# Superbot_LEDS.net
KiCad netlist of a schematic drawn in Altium Designer
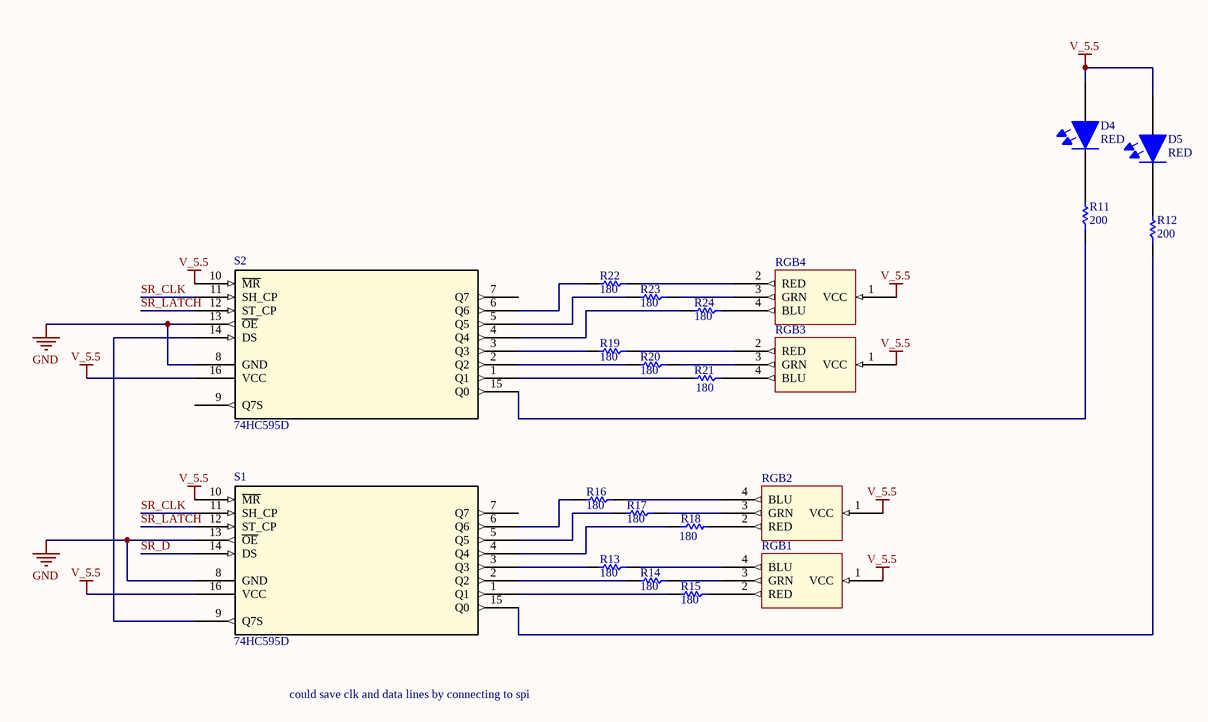
[diagram p0: Superbot_LEDS.SchDoc]

(export (version "E")
  (design (tool "Eeschema 10.0.6"))
  (components
    (comp (ref "D4")
      (value "RED")
      (footprint "LED0603")
      (description "LED")
      (libsource (lib "SuperBot_Schlib1") (part "LED"))
    )
    (comp (ref "D5")
      (value "RED")
      (footprint "LED0603")
      (description "LED")
      (libsource (lib "SuperBot_Schlib1") (part "LED"))
    )
    (comp (ref "R11")
      (value "200")
      (footprint "RES0603R")
      (description "Resistor")
      (libsource (lib "SuperBot_Schlib1") (part "R"))
    )
    (comp (ref "R12")
      (value "200")
      (footprint "RES0603R")
      (description "Resistor")
      (libsource (lib "SuperBot_Schlib1") (part "R"))
    )
    (comp (ref "R13")
      (value "180")
      (footprint "RES0603R")
      (description "Resistor")
      (libsource (lib "SuperBot_Schlib1") (part "R"))
    )
    (comp (ref "R14")
      (value "180")
      (footprint "RES0603R")
      (description "Resistor")
      (libsource (lib "SuperBot_Schlib1") (part "R"))
    )
    (comp (ref "R15")
      (value "180")
      (footprint "RES0603R")
      (description "Resistor")
      (libsource (lib "SuperBot_Schlib1") (part "R"))
    )
    (comp (ref "R16")
      (value "180")
      (footprint "RES0603R")
      (description "Resistor")
      (libsource (lib "SuperBot_Schlib1") (part "R"))
    )
    (comp (ref "R17")
      (value "180")
      (footprint "RES0603R")
      (description "Resistor")
      (libsource (lib "SuperBot_Schlib1") (part "R"))
    )
    (comp (ref "R18")
      (value "180")
      (footprint "RES0603R")
      (description "Resistor")
      (libsource (lib "SuperBot_Schlib1") (part "R"))
    )
    (comp (ref "R19")
      (value "180")
      (footprint "RES0603R")
      (description "Resistor")
      (libsource (lib "SuperBot_Schlib1") (part "R"))
    )
    (comp (ref "R20")
      (value "180")
      (footprint "RES0603R")
      (description "Resistor")
      (libsource (lib "SuperBot_Schlib1") (part "R"))
    )
    (comp (ref "R21")
      (value "180")
      (footprint "RES0603R")
      (description "Resistor")
      (libsource (lib "SuperBot_Schlib1") (part "R"))
    )
    (comp (ref "R22")
      (value "180")
      (footprint "RES0603R")
      (description "Resistor")
      (libsource (lib "SuperBot_Schlib1") (part "R"))
    )
    (comp (ref "R23")
      (value "180")
      (footprint "RES0603R")
      (description "Resistor")
      (libsource (lib "SuperBot_Schlib1") (part "R"))
    )
    (comp (ref "R24")
      (value "180")
      (footprint "RES0603R")
      (description "Resistor")
      (libsource (lib "SuperBot_Schlib1") (part "R"))
    )
    (comp (ref "RGB1")
      (value "~")
      (footprint "RGB LED")
      (fields
        (field (name "MANUFACTURER") "Cree Inc")
        (field (name "MANUFACTURER PART NUM") "CLV1L-FKB-CJMNQEGBB7673673")
      )
      (libsource (lib "SuperBot_Schlib1") (part "RGB LED"))
    )
    (comp (ref "RGB2")
      (value "~")
      (footprint "RGB LED")
      (fields
        (field (name "MANUFACTURER") "Cree Inc")
        (field (name "MANUFACTURER PART NUM") "CLV1L-FKB-CJMNQEGBB7673673")
      )
      (libsource (lib "SuperBot_Schlib1") (part "RGB LED"))
    )
    (comp (ref "RGB3")
      (value "~")
      (footprint "RGB LED")
      (fields
        (field (name "MANUFACTURER") "Cree Inc")
        (field (name "MANUFACTURER PART NUM") "CLV1L-FKB-CJMNQEGBB7673673")
      )
      (libsource (lib "") (part "RGB LED_1"))
    )
    (comp (ref "RGB4")
      (value "~")
      (footprint "RGB LED")
      (fields
        (field (name "MANUFACTURER") "Cree Inc")
        (field (name "MANUFACTURER PART NUM") "CLV1L-FKB-CJMNQEGBB7673673")
      )
      (libsource (lib "") (part "RGB LED_1"))
    )
    (comp (ref "S1")
      (value "74HC595D")
      (footprint "SOT109-1-M")
      (description "Shift Register")
      (libsource (lib "SuperBot_Schlib1") (part "74HC595D"))
    )
    (comp (ref "S2")
      (value "74HC595D")
      (footprint "SOT109-1-M")
      (description "Shift Register")
      (libsource (lib "SuperBot_Schlib1") (part "74HC595D"))
    )
  )
  (nets
    (net (code "1") (name "/SR_CLK") (class "Default")
      (node (ref "S1") (pin "11") (pinfunction "SH_CP_11") (pintype "input"))
      (node (ref "S2") (pin "11") (pinfunction "SH_CP_11") (pintype "input"))
    )
    (net (code "2") (name "/SR_D") (class "Default")
      (node (ref "S1") (pin "14") (pinfunction "DS_14") (pintype "input"))
    )
    (net (code "3") (name "/SR_LATCH") (class "Default")
      (node (ref "S1") (pin "12") (pinfunction "ST_CP_12") (pintype "input"))
      (node (ref "S2") (pin "12") (pinfunction "ST_CP_12") (pintype "input"))
    )
    (net (code "4") (name "GND") (class "Default")
      (node (ref "S1") (pin "13") (pinfunction "~{OE}_13") (pintype "output"))
      (node (ref "S1") (pin "8") (pinfunction "GND_8") (pintype "power_in"))
      (node (ref "S2") (pin "13") (pinfunction "~{OE}_13") (pintype "output"))
      (node (ref "S2") (pin "8") (pinfunction "GND_8") (pintype "power_in"))
    )
    (net (code "5") (name "Net-(D4-CATHODE)") (class "Default")
      (node (ref "D4") (pin "K") (pinfunction "CATHODE_K") (pintype "passive"))
      (node (ref "R11") (pin "2") (pintype "passive"))
    )
    (net (code "6") (name "Net-(D5-CATHODE)") (class "Default")
      (node (ref "D5") (pin "K") (pinfunction "CATHODE_K") (pintype "passive"))
      (node (ref "R12") (pin "2") (pintype "passive"))
    )
    (net (code "7") (name "Net-(RGB1-BLU)") (class "Default")
      (node (ref "R13") (pin "1") (pintype "passive"))
      (node (ref "RGB1") (pin "4") (pinfunction "BLU_4") (pintype "output"))
    )
    (net (code "8") (name "Net-(RGB1-GRN)") (class "Default")
      (node (ref "R14") (pin "1") (pintype "passive"))
      (node (ref "RGB1") (pin "3") (pinfunction "GRN_3") (pintype "output"))
    )
    (net (code "9") (name "Net-(RGB1-RED)") (class "Default")
      (node (ref "R15") (pin "1") (pintype "passive"))
      (node (ref "RGB1") (pin "2") (pinfunction "RED_2") (pintype "output"))
    )
    (net (code "10") (name "Net-(RGB2-BLU)") (class "Default")
      (node (ref "R16") (pin "1") (pintype "passive"))
      (node (ref "RGB2") (pin "4") (pinfunction "BLU_4") (pintype "output"))
    )
    (net (code "11") (name "Net-(RGB2-GRN)") (class "Default")
      (node (ref "R17") (pin "1") (pintype "passive"))
      (node (ref "RGB2") (pin "3") (pinfunction "GRN_3") (pintype "output"))
    )
    (net (code "12") (name "Net-(RGB2-RED)") (class "Default")
      (node (ref "R18") (pin "2") (pintype "passive"))
      (node (ref "RGB2") (pin "2") (pinfunction "RED_2") (pintype "output"))
    )
    (net (code "13") (name "Net-(RGB3-BLU)") (class "Default")
      (node (ref "R21") (pin "1") (pintype "passive"))
      (node (ref "RGB3") (pin "4") (pinfunction "BLU_4") (pintype "output"))
    )
    (net (code "14") (name "Net-(RGB3-GRN)") (class "Default")
      (node (ref "R20") (pin "1") (pintype "passive"))
      (node (ref "RGB3") (pin "3") (pinfunction "GRN_3") (pintype "output"))
    )
    (net (code "15") (name "Net-(RGB3-RED)") (class "Default")
      (node (ref "R19") (pin "1") (pintype "passive"))
      (node (ref "RGB3") (pin "2") (pinfunction "RED_2") (pintype "output"))
    )
    (net (code "16") (name "Net-(RGB4-BLU)") (class "Default")
      (node (ref "R24") (pin "1") (pintype "passive"))
      (node (ref "RGB4") (pin "4") (pinfunction "BLU_4") (pintype "output"))
    )
    (net (code "17") (name "Net-(RGB4-GRN)") (class "Default")
      (node (ref "R23") (pin "1") (pintype "passive"))
      (node (ref "RGB4") (pin "3") (pinfunction "GRN_3") (pintype "output"))
    )
    (net (code "18") (name "Net-(RGB4-RED)") (class "Default")
      (node (ref "R22") (pin "1") (pintype "passive"))
      (node (ref "RGB4") (pin "2") (pinfunction "RED_2") (pintype "output"))
    )
    (net (code "19") (name "Net-(S1-Q0)") (class "Default")
      (node (ref "R12") (pin "1") (pintype "passive"))
      (node (ref "S1") (pin "15") (pinfunction "Q0_15") (pintype "output"))
    )
    (net (code "20") (name "Net-(S1-Q1)") (class "Default")
      (node (ref "R15") (pin "2") (pintype "passive"))
      (node (ref "S1") (pin "1") (pinfunction "Q1_1") (pintype "output"))
    )
    (net (code "21") (name "Net-(S1-Q2)") (class "Default")
      (node (ref "R14") (pin "2") (pintype "passive"))
      (node (ref "S1") (pin "2") (pinfunction "Q2_2") (pintype "output"))
    )
    (net (code "22") (name "Net-(S1-Q3)") (class "Default")
      (node (ref "R13") (pin "2") (pintype "passive"))
      (node (ref "S1") (pin "3") (pinfunction "Q3_3") (pintype "output"))
    )
    (net (code "23") (name "Net-(S1-Q4)") (class "Default")
      (node (ref "R18") (pin "1") (pintype "passive"))
      (node (ref "S1") (pin "4") (pinfunction "Q4_4") (pintype "output"))
    )
    (net (code "24") (name "Net-(S1-Q5)") (class "Default")
      (node (ref "R17") (pin "2") (pintype "passive"))
      (node (ref "S1") (pin "5") (pinfunction "Q5_5") (pintype "output"))
    )
    (net (code "25") (name "Net-(S1-Q6)") (class "Default")
      (node (ref "R16") (pin "2") (pintype "passive"))
      (node (ref "S1") (pin "6") (pinfunction "Q6_6") (pintype "output"))
    )
    (net (code "26") (name "Net-(S1-Q7S)") (class "Default")
      (node (ref "S1") (pin "9") (pinfunction "Q7S_9") (pintype "output"))
      (node (ref "S2") (pin "14") (pinfunction "DS_14") (pintype "input"))
    )
    (net (code "27") (name "Net-(S2-Q0)") (class "Default")
      (node (ref "R11") (pin "1") (pintype "passive"))
      (node (ref "S2") (pin "15") (pinfunction "Q0_15") (pintype "output"))
    )
    (net (code "28") (name "Net-(S2-Q1)") (class "Default")
      (node (ref "R21") (pin "2") (pintype "passive"))
      (node (ref "S2") (pin "1") (pinfunction "Q1_1") (pintype "output"))
    )
    (net (code "29") (name "Net-(S2-Q2)") (class "Default")
      (node (ref "R20") (pin "2") (pintype "passive"))
      (node (ref "S2") (pin "2") (pinfunction "Q2_2") (pintype "output"))
    )
    (net (code "30") (name "Net-(S2-Q3)") (class "Default")
      (node (ref "R19") (pin "2") (pintype "passive"))
      (node (ref "S2") (pin "3") (pinfunction "Q3_3") (pintype "output"))
    )
    (net (code "31") (name "Net-(S2-Q4)") (class "Default")
      (node (ref "R24") (pin "2") (pintype "passive"))
      (node (ref "S2") (pin "4") (pinfunction "Q4_4") (pintype "output"))
    )
    (net (code "32") (name "Net-(S2-Q5)") (class "Default")
      (node (ref "R23") (pin "2") (pintype "passive"))
      (node (ref "S2") (pin "5") (pinfunction "Q5_5") (pintype "output"))
    )
    (net (code "33") (name "Net-(S2-Q6)") (class "Default")
      (node (ref "R22") (pin "2") (pintype "passive"))
      (node (ref "S2") (pin "6") (pinfunction "Q6_6") (pintype "output"))
    )
    (net (code "34") (name "V_5.5") (class "Default")
      (node (ref "D4") (pin "A") (pinfunction "ANODE_A") (pintype "passive"))
      (node (ref "D5") (pin "A") (pinfunction "ANODE_A") (pintype "passive"))
      (node (ref "RGB1") (pin "1") (pinfunction "VCC_1") (pintype "input"))
      (node (ref "RGB2") (pin "1") (pinfunction "VCC_1") (pintype "input"))
      (node (ref "RGB3") (pin "1") (pinfunction "VCC_1") (pintype "input"))
      (node (ref "RGB4") (pin "1") (pinfunction "VCC_1") (pintype "input"))
      (node (ref "S1") (pin "10") (pinfunction "~{MR}_10") (pintype "input"))
      (node (ref "S1") (pin "16") (pinfunction "VCC_16") (pintype "power_in"))
      (node (ref "S2") (pin "10") (pinfunction "~{MR}_10") (pintype "input"))
      (node (ref "S2") (pin "16") (pinfunction "VCC_16") (pintype "power_in"))
    )
    (net (code "35") (name "unconnected-(S1-Q7-Pad7)") (class "Default")
      (node (ref "S1") (pin "7") (pinfunction "Q7_7") (pintype "output"))
    )
    (net (code "36") (name "unconnected-(S2-Q7-Pad7)") (class "Default")
      (node (ref "S2") (pin "7") (pinfunction "Q7_7") (pintype "output"))
    )
    (net (code "37") (name "unconnected-(S2-Q7S-Pad9)") (class "Default")
      (node (ref "S2") (pin "9") (pinfunction "Q7S_9") (pintype "output"))
    )
  )
)
